# PTN78060W.net
KiCad netlist of a schematic drawn in EAGLE
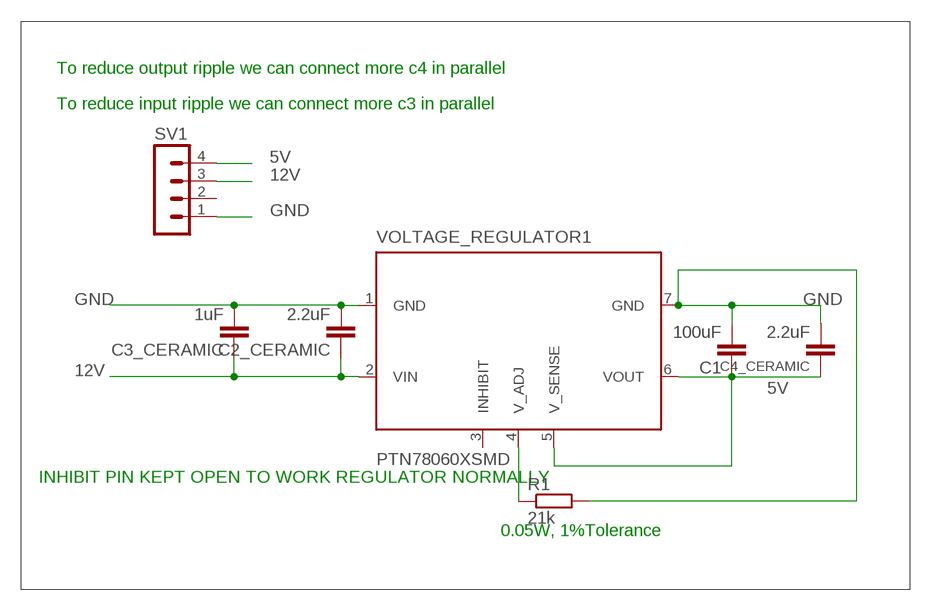
[diagram p0: schematic, sheet 1]

(export (version "E")
  (design (tool "Eeschema 10.0.6"))
  (components
    (comp (ref "C1")
      (value "100uF")
      (footprint "eagle-import:C0805")
      (libsource (lib "eagle-import") (part "C-EUC0805"))
    )
    (comp (ref "C2_CERAMIC")
      (value "2.2uF")
      (footprint "eagle-import:C0805")
      (libsource (lib "eagle-import") (part "C-EUC0805"))
    )
    (comp (ref "C3_CERAMIC")
      (value "1uF")
      (footprint "eagle-import:C0805")
      (libsource (lib "eagle-import") (part "C-EUC0805"))
    )
    (comp (ref "C4_CERAMIC")
      (value "2.2uF")
      (footprint "eagle-import:C0805")
      (libsource (lib "eagle-import") (part "C-EUC0805"))
    )
    (comp (ref "R1")
      (value "21k")
      (footprint "eagle-import:R0805")
      (libsource (lib "eagle-import") (part "R-EU_R0805"))
    )
    (comp (ref "SV1")
      (value "MA04-1")
      (footprint "eagle-import:MA04-1")
      (libsource (lib "eagle-import") (part "MA04-1"))
    )
    (comp (ref "VOLTAGE_REGULATOR1")
      (value "PTN78060XSMD")
      (footprint "eagle-import:PTN78060X_SMD")
      (libsource (lib "eagle-import") (part "PTN78060XSMD"))
    )
  )
  (nets
    (net (code "1") (name "/5V") (class "Default")
      (node (ref "C1") (pin "1") (pinfunction "1_1") (pintype "passive"))
      (node (ref "C4_CERAMIC") (pin "1") (pinfunction "1_1") (pintype "passive"))
      (node (ref "SV1") (pin "4") (pinfunction "4_4") (pintype "passive"))
      (node (ref "VOLTAGE_REGULATOR1") (pin "5") (pinfunction "V_SENSE_5") (pintype "bidirectional"))
      (node (ref "VOLTAGE_REGULATOR1") (pin "6") (pinfunction "VOUT_6") (pintype "bidirectional"))
    )
    (net (code "2") (name "/12V") (class "Default")
      (node (ref "C2_CERAMIC") (pin "1") (pinfunction "1_1") (pintype "passive"))
      (node (ref "C3_CERAMIC") (pin "1") (pinfunction "1_1") (pintype "passive"))
      (node (ref "SV1") (pin "3") (pinfunction "3_3") (pintype "passive"))
      (node (ref "VOLTAGE_REGULATOR1") (pin "2") (pinfunction "VIN_2") (pintype "bidirectional"))
    )
    (net (code "3") (name "/GND") (class "Default")
      (node (ref "C1") (pin "2") (pinfunction "2_2") (pintype "passive"))
      (node (ref "C2_CERAMIC") (pin "2") (pinfunction "2_2") (pintype "passive"))
      (node (ref "C3_CERAMIC") (pin "2") (pinfunction "2_2") (pintype "passive"))
      (node (ref "C4_CERAMIC") (pin "2") (pinfunction "2_2") (pintype "passive"))
      (node (ref "R1") (pin "2") (pinfunction "2_2") (pintype "passive"))
      (node (ref "SV1") (pin "1") (pinfunction "1_1") (pintype "passive"))
      (node (ref "VOLTAGE_REGULATOR1") (pin "1") (pinfunction "GND_1") (pintype "bidirectional"))
      (node (ref "VOLTAGE_REGULATOR1") (pin "7") (pinfunction "GND_7") (pintype "bidirectional"))
    )
    (net (code "4") (name "Net-(VOLTAGE_REGULATOR1-V_ADJ)") (class "Default")
      (node (ref "R1") (pin "1") (pinfunction "1_1") (pintype "passive"))
      (node (ref "VOLTAGE_REGULATOR1") (pin "4") (pinfunction "V_ADJ_4") (pintype "bidirectional"))
    )
    (net (code "5") (name "unconnected-(SV1-Pad2)") (class "Default")
      (node (ref "SV1") (pin "2") (pinfunction "2_2") (pintype "passive"))
    )
    (net (code "6") (name "unconnected-(VOLTAGE_REGULATOR1-INHIBIT-Pad3)") (class "Default")
      (node (ref "VOLTAGE_REGULATOR1") (pin "3") (pinfunction "INHIBIT_3") (pintype "bidirectional"))
    )
  )
)
